# Nozzle_Magazine_v2.net
KiCad netlist of a schematic drawn in EAGLE
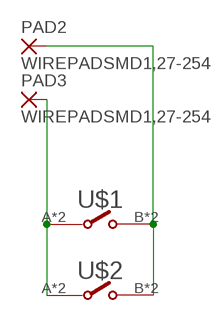
[diagram p0: schematic, sheet 1]

(export (version "E")
  (design (tool "Eeschema 10.0.6"))
  (components
    (comp (ref "PAD2")
      (value "WIREPADSMD1,27-254")
      (footprint "eagle-import:SMD1,27-2,54")
      (libsource (lib "eagle-import") (part "WIREPADSMD1,27-254"))
    )
    (comp (ref "PAD3")
      (value "WIREPADSMD1,27-254")
      (footprint "eagle-import:SMD1,27-2,54")
      (libsource (lib "eagle-import") (part "WIREPADSMD1,27-254"))
    )
    (comp (ref "U$1")
      (value "SWITCH_LIMIT_HDP001L")
      (footprint "eagle-import:SWITCH_LIMIT_HDP001L")
      (libsource (lib "eagle-import") (part "SWITCH_LIMIT_HDP001L"))
    )
    (comp (ref "U$2")
      (value "SWITCH_LIMIT_HDP001L")
      (footprint "eagle-import:SWITCH_LIMIT_HDP001L")
      (libsource (lib "eagle-import") (part "SWITCH_LIMIT_HDP001L"))
    )
  )
  (nets
    (net (code "1") (name "Net-(PAD2-P)") (class "Default")
      (node (ref "PAD2") (pin "1") (pinfunction "P_1") (pintype "passive"))
      (node (ref "U$1") (pin "B") (pinfunction "2_B") (pintype "passive"))
      (node (ref "U$1") (pin "D") (pinfunction "2_D") (pintype "passive"))
      (node (ref "U$2") (pin "B") (pinfunction "2_B") (pintype "passive"))
      (node (ref "U$2") (pin "D") (pinfunction "2_D") (pintype "passive"))
    )
    (net (code "2") (name "Net-(PAD3-P)") (class "Default")
      (node (ref "PAD3") (pin "1") (pinfunction "P_1") (pintype "passive"))
      (node (ref "U$1") (pin "A") (pinfunction "1_A") (pintype "passive"))
      (node (ref "U$1") (pin "C") (pinfunction "1_C") (pintype "passive"))
      (node (ref "U$2") (pin "A") (pinfunction "1_A") (pintype "passive"))
      (node (ref "U$2") (pin "C") (pinfunction "1_C") (pintype "passive"))
    )
  )
)
